# SCH_GroeiAcademie-v0_10_0_2026-07-24.net
KiCad netlist of a schematic drawn in EasyEDA
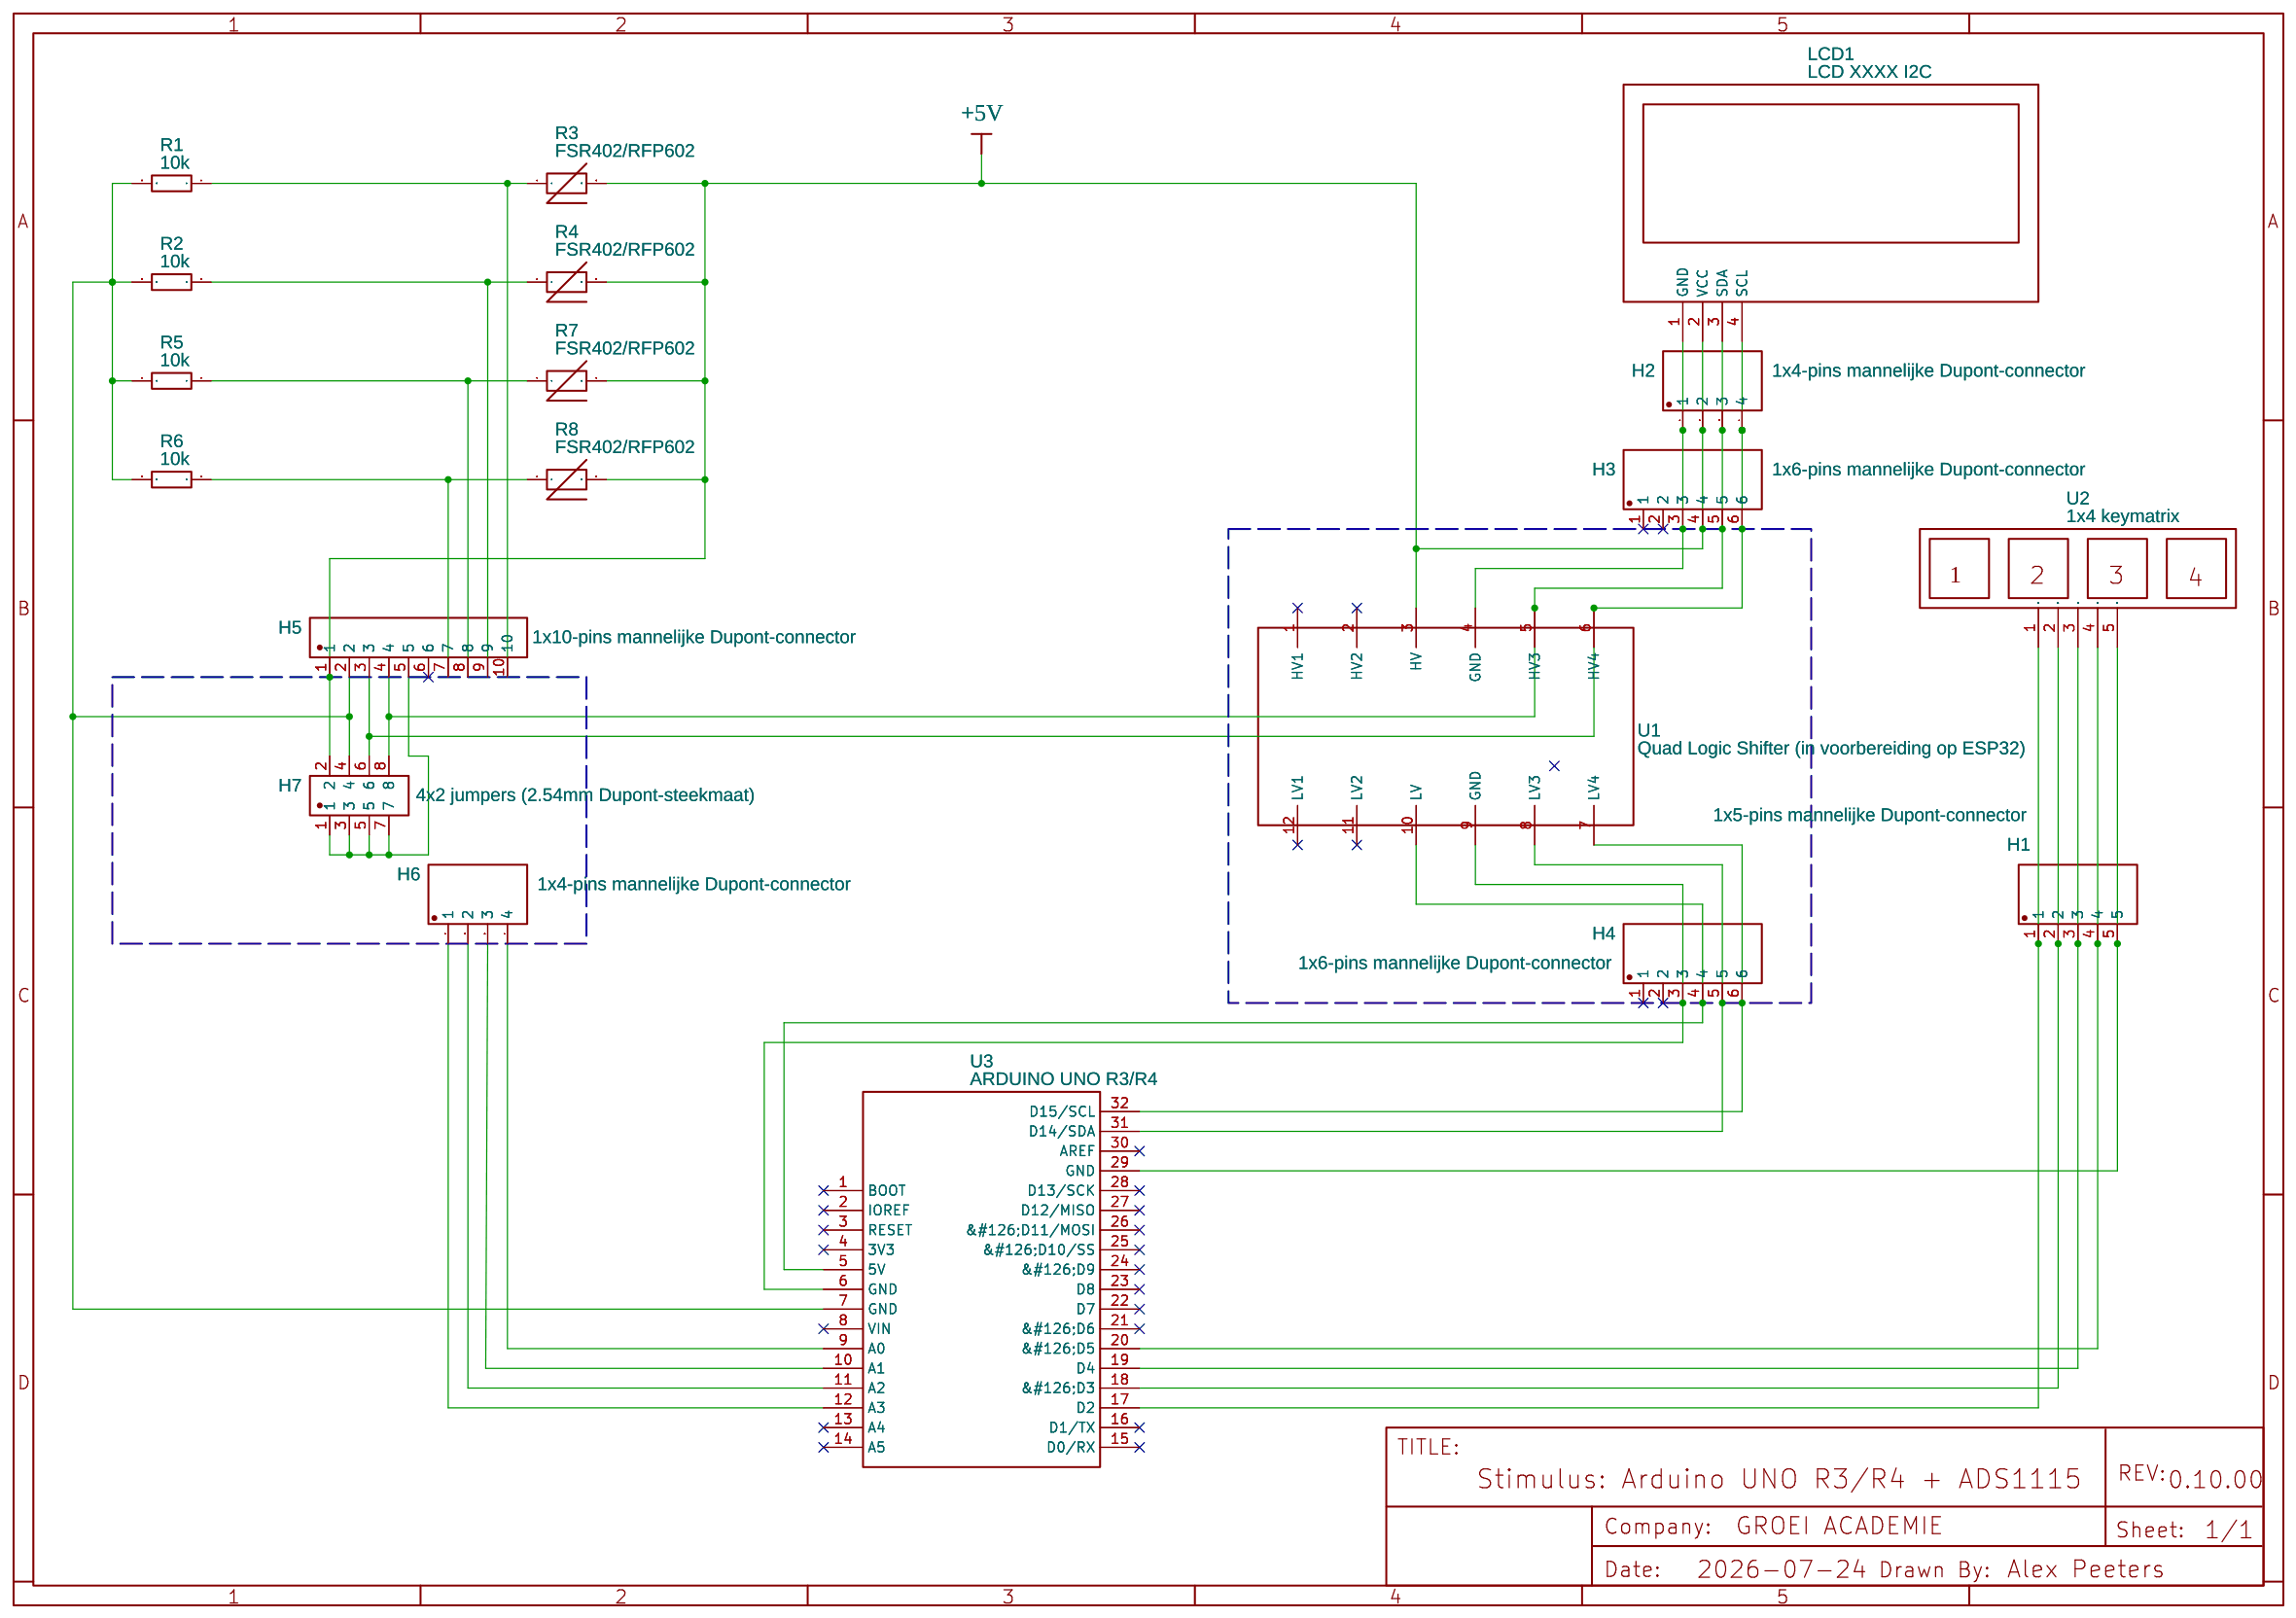
[diagram p0: schematic sheet]

(export (version "E")
  (design (tool "Eeschema 10.0.6"))
  (components
    (comp (ref "H1")
      (value "1x5-pins mannelijke Dupont-connector")
      (fields (field (name "Manufacturer Part") "B-2100S05P-A110") (field (name "Manufacturer") "Ckmtw(灿科盟)"))
      (libsource (lib "") (part "210S-1*5P L=11.6MMGold-plated black"))
    )
    (comp (ref "H2")
      (value "1x4-pins mannelijke Dupont-connector")
      (fields (field (name "Manufacturer Part") "B-2100S04P-A110") (field (name "Manufacturer") "Ckmtw(灿科盟)"))
      (libsource (lib "") (part "Header-Male-2.54_1x4"))
    )
    (comp (ref "H3")
      (value "1x6-pins mannelijke Dupont-connector")
      (fields (field (name "Manufacturer Part") "B-2100S06P-A110") (field (name "Manufacturer") "Ckmtw(灿科盟)"))
      (libsource (lib "") (part "210S-1*6P L=11.6MMGold-plated black"))
    )
    (comp (ref "H4")
      (value "1x6-pins mannelijke Dupont-connector")
      (fields (field (name "Manufacturer Part") "B-2100S06P-A110") (field (name "Manufacturer") "Ckmtw(灿科盟)"))
      (libsource (lib "") (part "210S-1*6P L=11.6MMGold-plated black"))
    )
    (comp (ref "H5")
      (value "1x10-pins mannelijke Dupont-connector")
      (fields (field (name "Manufacturer Part") "2.54-1*10") (field (name "Manufacturer") "ZHOURI(洲日)"))
      (libsource (lib "") (part "2.54-1*10"))
    )
    (comp (ref "H6")
      (value "1x4-pins mannelijke Dupont-connector")
      (fields (field (name "Manufacturer Part") "B-2100S04P-A110") (field (name "Manufacturer") "Ckmtw(灿科盟)"))
      (libsource (lib "") (part "Header-Male-2.54_1x4"))
    )
    (comp (ref "H7")
      (value "4x2 jumpers (2.54mm Dupont-steekmaat)")
      (fields (field (name "Manufacturer Part") "2.54-2*4P立贴针") (field (name "Manufacturer") "BOOMELE(博穆精密)"))
      (libsource (lib "") (part "2.54-2*4P立贴针"))
    )
    (comp (ref "LCD1") (value "LCD XXXX I2C") (libsource (lib "") (part "I2CLCD16X2_N")))
    (comp (ref "R1")
      (value "10k")
      (fields (field (name "Manufacturer") "Made in China"))
      (libsource (lib "") (part "330Ω (331) ±5%"))
    )
    (comp (ref "R2")
      (value "10k")
      (fields (field (name "Manufacturer") "Made in China"))
      (libsource (lib "") (part "330Ω (331) ±5%"))
    )
    (comp (ref "R3") (value "FSR402/RFP602") (libsource (lib "") (part "FSR402-OPCION1")))
    (comp (ref "R4") (value "FSR402/RFP602") (libsource (lib "") (part "FSR402-OPCION1")))
    (comp (ref "R5")
      (value "10k")
      (fields (field (name "Manufacturer") "Made in China"))
      (libsource (lib "") (part "330Ω (331) ±5%"))
    )
    (comp (ref "R6")
      (value "10k")
      (fields (field (name "Manufacturer") "Made in China"))
      (libsource (lib "") (part "330Ω (331) ±5%"))
    )
    (comp (ref "R7") (value "FSR402/RFP602") (libsource (lib "") (part "FSR402-OPCION1")))
    (comp (ref "R8") (value "FSR402/RFP602") (libsource (lib "") (part "FSR402-OPCION1")))
    (comp (ref "U1")
      (value "Quad Logic Shifter (in voorbereiding op ESP32)")
      (libsource (lib "") (part "Quad Logic Shifter"))
    )
    (comp (ref "U2") (value "1x4 keymatrix") (libsource (lib "") (part "Клавиатура 4*4")))
    (comp (ref "U3") (value "ARDUINO UNO R3/R4") (libsource (lib "") (part "ARDUINO UNO R4 MINIMA")))
  )
  (nets
    (net (code "1") (name "+5V") (class "Default")
      (node (ref "H2") (pin "2") (pinfunction "2_2") (pintype "unspecified"))
      (node (ref "H3") (pin "4") (pinfunction "4_4") (pintype "unspecified"))
      (node (ref "H5") (pin "1") (pinfunction "1_1") (pintype "unspecified"))
      (node (ref "H7") (pin "2") (pinfunction "2_2") (pintype "unspecified"))
      (node (ref "LCD1") (pin "2") (pinfunction "VCC_2") (pintype "unspecified"))
      (node (ref "R3") (pin "2") (pinfunction "2_2") (pintype "unspecified"))
      (node (ref "R4") (pin "2") (pinfunction "2_2") (pintype "unspecified"))
      (node (ref "R7") (pin "2") (pinfunction "2_2") (pintype "unspecified"))
      (node (ref "R8") (pin "2") (pinfunction "2_2") (pintype "unspecified"))
      (node (ref "U1") (pin "3") (pinfunction "HV_3") (pintype "unspecified"))
    )
    (net (code "2") (name "Net-(H4-Pad3)") (class "Default")
      (node (ref "H4") (pin "3") (pinfunction "3_3") (pintype "unspecified"))
      (node (ref "U1") (pin "9") (pinfunction "GND_9") (pintype "unspecified"))
      (node (ref "U3") (pin "6") (pinfunction "GND_6") (pintype "unspecified"))
    )
    (net (code "3") (name "Net-(H5-Pad2)") (class "Default")
      (node (ref "H5") (pin "2") (pinfunction "2_2") (pintype "unspecified"))
      (node (ref "H7") (pin "4") (pinfunction "4_4") (pintype "unspecified"))
      (node (ref "R1") (pin "2") (pinfunction "2_2") (pintype "unspecified"))
      (node (ref "R2") (pin "2") (pinfunction "2_2") (pintype "unspecified"))
      (node (ref "R5") (pin "2") (pinfunction "2_2") (pintype "unspecified"))
      (node (ref "R6") (pin "2") (pinfunction "2_2") (pintype "unspecified"))
      (node (ref "U3") (pin "7") (pinfunction "GND_7") (pintype "unspecified"))
    )
    (net (code "4") (name "Net-(H5-Pad5)") (class "Default")
      (node (ref "H5") (pin "5") (pinfunction "5_5") (pintype "unspecified"))
      (node (ref "H7") (pin "1") (pinfunction "1_1") (pintype "unspecified"))
      (node (ref "H7") (pin "3") (pinfunction "3_3") (pintype "unspecified"))
      (node (ref "H7") (pin "5") (pinfunction "5_5") (pintype "unspecified"))
      (node (ref "H7") (pin "7") (pinfunction "7_7") (pintype "unspecified"))
    )
    (net (code "5") (name "Net-(H5-Pad7)") (class "Default")
      (node (ref "H5") (pin "7") (pinfunction "7_7") (pintype "unspecified"))
      (node (ref "R6") (pin "1") (pinfunction "1_1") (pintype "unspecified"))
      (node (ref "R8") (pin "1") (pinfunction "1_1") (pintype "unspecified"))
    )
    (net (code "6") (name "Net-(H5-Pad8)") (class "Default")
      (node (ref "H5") (pin "8") (pinfunction "8_8") (pintype "unspecified"))
      (node (ref "R5") (pin "1") (pinfunction "1_1") (pintype "unspecified"))
      (node (ref "R7") (pin "1") (pinfunction "1_1") (pintype "unspecified"))
    )
    (net (code "7") (name "Net-(H5-Pad9)") (class "Default")
      (node (ref "H5") (pin "9") (pinfunction "9_9") (pintype "unspecified"))
      (node (ref "R2") (pin "1") (pinfunction "1_1") (pintype "unspecified"))
      (node (ref "R4") (pin "1") (pinfunction "1_1") (pintype "unspecified"))
    )
    (net (code "8") (name "Net-(H5-Pad10)") (class "Default")
      (node (ref "H5") (pin "10") (pinfunction "10_10") (pintype "unspecified"))
      (node (ref "R1") (pin "1") (pinfunction "1_1") (pintype "unspecified"))
      (node (ref "R3") (pin "1") (pinfunction "1_1") (pintype "unspecified"))
    )
    (net (code "9") (name "Net-(LCD1-GND)") (class "Default")
      (node (ref "H2") (pin "1") (pinfunction "1_1") (pintype "unspecified"))
      (node (ref "H3") (pin "3") (pinfunction "3_3") (pintype "unspecified"))
      (node (ref "LCD1") (pin "1") (pinfunction "GND_1") (pintype "unspecified"))
      (node (ref "U1") (pin "4") (pinfunction "GND_4") (pintype "unspecified"))
    )
    (net (code "10") (name "Net-(LCD1-SCL)") (class "Default")
      (node (ref "H2") (pin "4") (pinfunction "4_4") (pintype "unspecified"))
      (node (ref "H3") (pin "6") (pinfunction "6_6") (pintype "unspecified"))
      (node (ref "H5") (pin "3") (pinfunction "3_3") (pintype "unspecified"))
      (node (ref "H7") (pin "6") (pinfunction "6_6") (pintype "unspecified"))
      (node (ref "LCD1") (pin "4") (pinfunction "SCL_4") (pintype "unspecified"))
      (node (ref "U1") (pin "6") (pinfunction "HV4_6") (pintype "unspecified"))
    )
    (net (code "11") (name "Net-(LCD1-SDA)") (class "Default")
      (node (ref "H2") (pin "3") (pinfunction "3_3") (pintype "unspecified"))
      (node (ref "H3") (pin "5") (pinfunction "5_5") (pintype "unspecified"))
      (node (ref "H5") (pin "4") (pinfunction "4_4") (pintype "unspecified"))
      (node (ref "H7") (pin "8") (pinfunction "8_8") (pintype "unspecified"))
      (node (ref "LCD1") (pin "3") (pinfunction "SDA_3") (pintype "unspecified"))
      (node (ref "U1") (pin "5") (pinfunction "HV3_5") (pintype "unspecified"))
    )
    (net (code "12") (name "Net-(U1-LV)") (class "Default")
      (node (ref "H4") (pin "4") (pinfunction "4_4") (pintype "unspecified"))
      (node (ref "U1") (pin "10") (pinfunction "LV_10") (pintype "unspecified"))
      (node (ref "U3") (pin "5") (pinfunction "5V_5") (pintype "unspecified"))
    )
    (net (code "13") (name "Net-(U1-LV3)") (class "Default")
      (node (ref "H4") (pin "5") (pinfunction "5_5") (pintype "unspecified"))
      (node (ref "U1") (pin "8") (pinfunction "LV3_8") (pintype "unspecified"))
      (node (ref "U3") (pin "31") (pinfunction "D14/SDA_31") (pintype "unspecified"))
    )
    (net (code "14") (name "Net-(U1-LV4)") (class "Default")
      (node (ref "H4") (pin "6") (pinfunction "6_6") (pintype "unspecified"))
      (node (ref "U1") (pin "7") (pinfunction "LV4_7") (pintype "unspecified"))
      (node (ref "U3") (pin "32") (pinfunction "D15/SCL_32") (pintype "unspecified"))
    )
    (net (code "15") (name "Net-(U2-C1)") (class "Default")
      (node (ref "H1") (pin "1") (pinfunction "1_1") (pintype "unspecified"))
      (node (ref "U2") (pin "1") (pinfunction "C1_1") (pintype "unspecified"))
      (node (ref "U3") (pin "17") (pinfunction "D2_17") (pintype "unspecified"))
    )
    (net (code "16") (name "Net-(U2-C2)") (class "Default")
      (node (ref "H1") (pin "2") (pinfunction "2_2") (pintype "unspecified"))
      (node (ref "U2") (pin "2") (pinfunction "C2_2") (pintype "unspecified"))
      (node (ref "U3") (pin "18") (pinfunction "&#126;D3_18") (pintype "unspecified"))
    )
    (net (code "17") (name "Net-(U2-C3)") (class "Default")
      (node (ref "H1") (pin "3") (pinfunction "3_3") (pintype "unspecified"))
      (node (ref "U2") (pin "3") (pinfunction "C3_3") (pintype "unspecified"))
      (node (ref "U3") (pin "19") (pinfunction "D4_19") (pintype "unspecified"))
    )
    (net (code "18") (name "Net-(U2-R1)") (class "Default")
      (node (ref "H1") (pin "4") (pinfunction "4_4") (pintype "unspecified"))
      (node (ref "U2") (pin "4") (pinfunction "R1_4") (pintype "unspecified"))
      (node (ref "U3") (pin "20") (pinfunction "&#126;D5_20") (pintype "unspecified"))
    )
    (net (code "19") (name "Net-(U2-R2)") (class "Default")
      (node (ref "H1") (pin "5") (pinfunction "5_5") (pintype "unspecified"))
      (node (ref "U2") (pin "5") (pinfunction "R2_5") (pintype "unspecified"))
      (node (ref "U3") (pin "29") (pinfunction "GND_29") (pintype "unspecified"))
    )
    (net (code "20") (name "Net-(U3-A0)") (class "Default")
      (node (ref "H6") (pin "4") (pinfunction "4_4") (pintype "unspecified"))
      (node (ref "U3") (pin "9") (pinfunction "A0_9") (pintype "unspecified"))
    )
    (net (code "21") (name "Net-(U3-A1)") (class "Default")
      (node (ref "H6") (pin "3") (pinfunction "3_3") (pintype "unspecified"))
      (node (ref "U3") (pin "10") (pinfunction "A1_10") (pintype "unspecified"))
    )
    (net (code "22") (name "Net-(U3-A2)") (class "Default")
      (node (ref "H6") (pin "2") (pinfunction "2_2") (pintype "unspecified"))
      (node (ref "U3") (pin "11") (pinfunction "A2_11") (pintype "unspecified"))
    )
    (net (code "23") (name "Net-(U3-A3)") (class "Default")
      (node (ref "H6") (pin "1") (pinfunction "1_1") (pintype "unspecified"))
      (node (ref "U3") (pin "12") (pinfunction "A3_12") (pintype "unspecified"))
    )
    (net (code "24") (name "unconnected-(H3-Pad1)") (class "Default")
      (node (ref "H3") (pin "1") (pinfunction "1_1") (pintype "unspecified+no_connect"))
    )
    (net (code "25") (name "unconnected-(H3-Pad2)") (class "Default")
      (node (ref "H3") (pin "2") (pinfunction "2_2") (pintype "unspecified+no_connect"))
    )
    (net (code "26") (name "unconnected-(H4-Pad1)") (class "Default")
      (node (ref "H4") (pin "1") (pinfunction "1_1") (pintype "unspecified+no_connect"))
    )
    (net (code "27") (name "unconnected-(H4-Pad2)") (class "Default")
      (node (ref "H4") (pin "2") (pinfunction "2_2") (pintype "unspecified+no_connect"))
    )
    (net (code "28") (name "unconnected-(H5-Pad6)") (class "Default")
      (node (ref "H5") (pin "6") (pinfunction "6_6") (pintype "unspecified+no_connect"))
    )
    (net (code "29") (name "unconnected-(U1-HV1-Pad1)") (class "Default")
      (node (ref "U1") (pin "1") (pinfunction "HV1_1") (pintype "unspecified+no_connect"))
    )
    (net (code "30") (name "unconnected-(U1-HV2-Pad2)") (class "Default")
      (node (ref "U1") (pin "2") (pinfunction "HV2_2") (pintype "unspecified+no_connect"))
    )
    (net (code "31") (name "unconnected-(U1-LV1-Pad12)") (class "Default")
      (node (ref "U1") (pin "12") (pinfunction "LV1_12") (pintype "unspecified+no_connect"))
    )
    (net (code "32") (name "unconnected-(U1-LV2-Pad11)") (class "Default")
      (node (ref "U1") (pin "11") (pinfunction "LV2_11") (pintype "unspecified+no_connect"))
    )
    (net (code "33") (name "unconnected-(U3-&#126;D6-Pad21)") (class "Default")
      (node (ref "U3") (pin "21") (pinfunction "&#126;D6_21") (pintype "unspecified+no_connect"))
    )
    (net (code "34") (name "unconnected-(U3-&#126;D9-Pad24)") (class "Default")
      (node (ref "U3") (pin "24") (pinfunction "&#126;D9_24") (pintype "unspecified+no_connect"))
    )
    (net (code "35") (name "unconnected-(U3-&#126;D10{slash}SS-Pad25)") (class "Default")
      (node (ref "U3") (pin "25") (pinfunction "&#126;D10/SS_25") (pintype "unspecified+no_connect"))
    )
    (net (code "36") (name "unconnected-(U3-&#126;D11{slash}MOSI-Pad26)") (class "Default")
      (node (ref "U3") (pin "26") (pinfunction "&#126;D11/MOSI_26") (pintype "unspecified+no_connect"))
    )
    (net (code "37") (name "unconnected-(U3-3V3-Pad4)") (class "Default")
      (node (ref "U3") (pin "4") (pinfunction "3V3_4") (pintype "unspecified+no_connect"))
    )
    (net (code "38") (name "unconnected-(U3-A4-Pad13)") (class "Default")
      (node (ref "U3") (pin "13") (pinfunction "A4_13") (pintype "unspecified+no_connect"))
    )
    (net (code "39") (name "unconnected-(U3-A5-Pad14)") (class "Default")
      (node (ref "U3") (pin "14") (pinfunction "A5_14") (pintype "unspecified+no_connect"))
    )
    (net (code "40") (name "unconnected-(U3-AREF-Pad30)") (class "Default")
      (node (ref "U3") (pin "30") (pinfunction "AREF_30") (pintype "unspecified+no_connect"))
    )
    (net (code "41") (name "unconnected-(U3-BOOT-Pad1)") (class "Default")
      (node (ref "U3") (pin "1") (pinfunction "BOOT_1") (pintype "unspecified+no_connect"))
    )
    (net (code "42") (name "unconnected-(U3-D0{slash}RX-Pad15)") (class "Default")
      (node (ref "U3") (pin "15") (pinfunction "D0/RX_15") (pintype "unspecified+no_connect"))
    )
    (net (code "43") (name "unconnected-(U3-D1{slash}TX-Pad16)") (class "Default")
      (node (ref "U3") (pin "16") (pinfunction "D1/TX_16") (pintype "unspecified+no_connect"))
    )
    (net (code "44") (name "unconnected-(U3-D7-Pad22)") (class "Default")
      (node (ref "U3") (pin "22") (pinfunction "D7_22") (pintype "unspecified+no_connect"))
    )
    (net (code "45") (name "unconnected-(U3-D8-Pad23)") (class "Default")
      (node (ref "U3") (pin "23") (pinfunction "D8_23") (pintype "unspecified+no_connect"))
    )
    (net (code "46") (name "unconnected-(U3-D12{slash}MISO-Pad27)") (class "Default")
      (node (ref "U3") (pin "27") (pinfunction "D12/MISO_27") (pintype "unspecified+no_connect"))
    )
    (net (code "47") (name "unconnected-(U3-D13{slash}SCK-Pad28)") (class "Default")
      (node (ref "U3") (pin "28") (pinfunction "D13/SCK_28") (pintype "unspecified+no_connect"))
    )
    (net (code "48") (name "unconnected-(U3-IOREF-Pad2)") (class "Default")
      (node (ref "U3") (pin "2") (pinfunction "IOREF_2") (pintype "unspecified+no_connect"))
    )
    (net (code "49") (name "unconnected-(U3-RESET-Pad3)") (class "Default")
      (node (ref "U3") (pin "3") (pinfunction "RESET_3") (pintype "unspecified+no_connect"))
    )
    (net (code "50") (name "unconnected-(U3-VIN-Pad8)") (class "Default")
      (node (ref "U3") (pin "8") (pinfunction "VIN_8") (pintype "unspecified+no_connect"))
    )
  )
)
